# MCU.net
KiCad netlist of a schematic drawn in Altium Designer
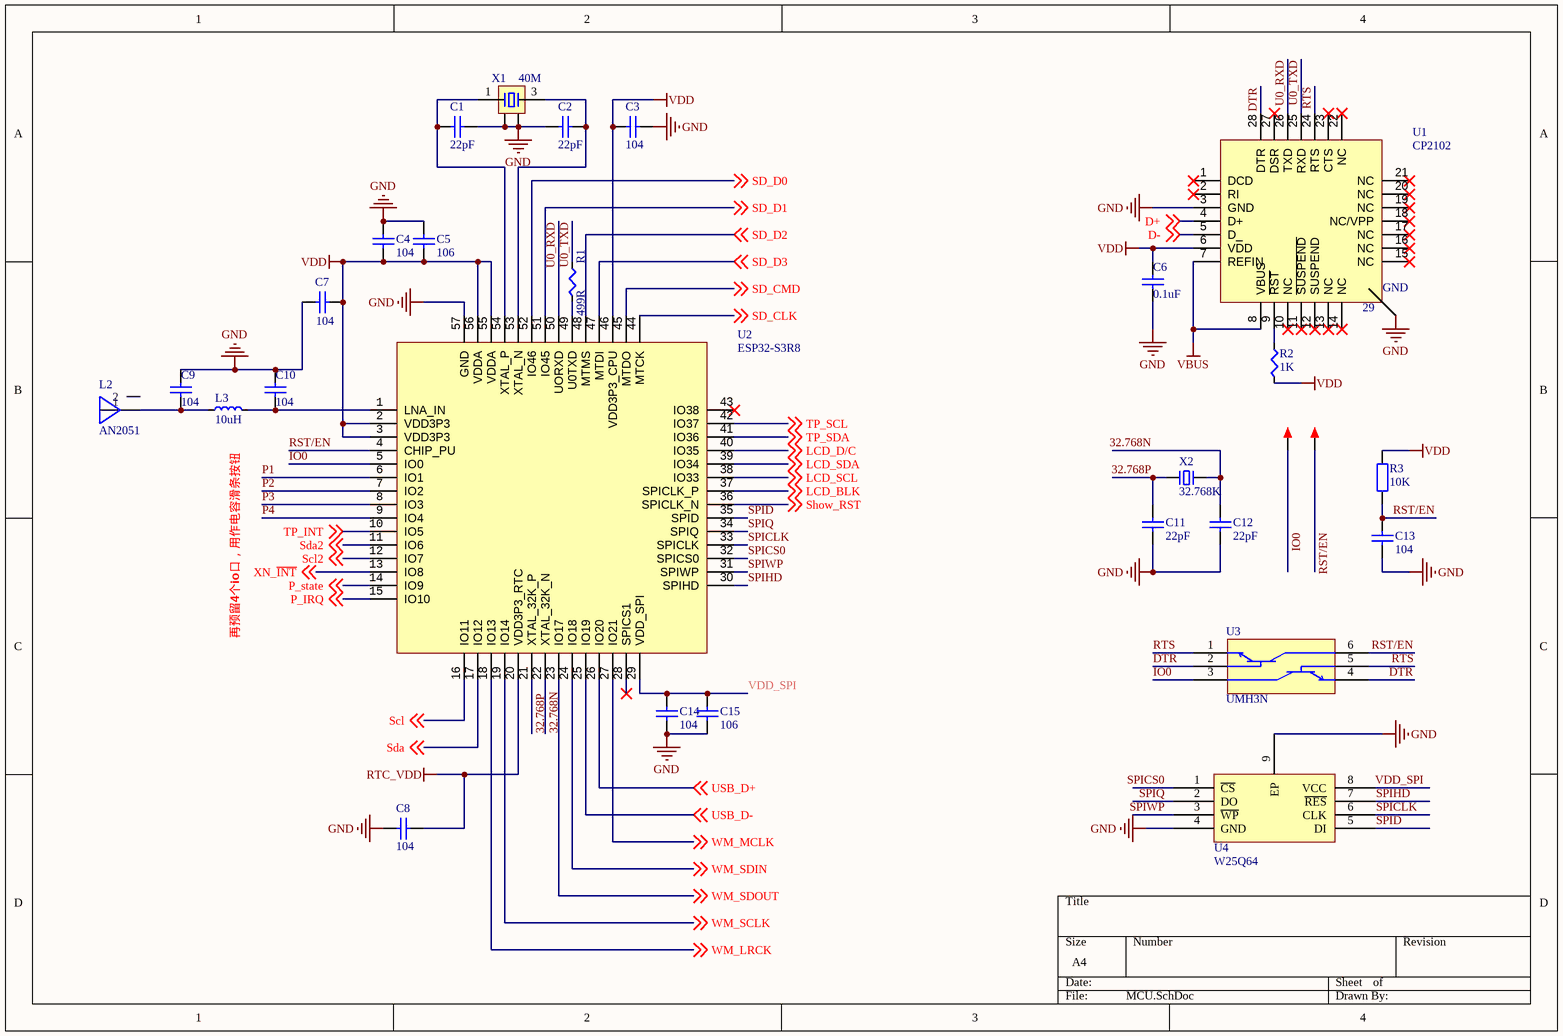
[diagram p0: MCU.SchDoc]

(export (version "E")
  (design (tool "Eeschema 10.0.6"))
  (components
    (comp (ref "C1")
      (value "22pF")
      (footprint "C 0603_L")
      (description "贴片电容")
      (libsource (lib "0.1 - 电阻-电容-电感") (part "C"))
    )
    (comp (ref "C2")
      (value "22pF")
      (footprint "C 0603_L")
      (description "贴片电容")
      (libsource (lib "0.1 - 电阻-电容-电感") (part "C"))
    )
    (comp (ref "C3")
      (value "104")
      (footprint "C 0603_L")
      (description "贴片电容")
      (libsource (lib "0.1 - 电阻-电容-电感") (part "C"))
    )
    (comp (ref "C4")
      (value "104")
      (footprint "C 0603_L")
      (description "贴片电容")
      (libsource (lib "0.1 - 电阻-电容-电感") (part "C"))
    )
    (comp (ref "C5")
      (value "106")
      (footprint "C 0603_L")
      (description "贴片电容")
      (libsource (lib "0.1 - 电阻-电容-电感") (part "C"))
    )
    (comp (ref "C6")
      (value "0.1uF")
      (footprint "C 0603_L")
      (description "贴片电容")
      (libsource (lib "0.1 - 电阻-电容-电感") (part "C"))
    )
    (comp (ref "C7")
      (value "104")
      (footprint "C 0603_L")
      (description "贴片电容")
      (libsource (lib "0.1 - 电阻-电容-电感") (part "C"))
    )
    (comp (ref "C8")
      (value "104")
      (footprint "C 0603_L")
      (description "贴片电容")
      (libsource (lib "0.1 - 电阻-电容-电感") (part "C"))
    )
    (comp (ref "C9")
      (value "104")
      (footprint "C 0603_L")
      (description "贴片电容")
      (libsource (lib "0.1 - 电阻-电容-电感") (part "C"))
    )
    (comp (ref "C10")
      (value "104")
      (footprint "C 0603_L")
      (description "贴片电容")
      (libsource (lib "0.1 - 电阻-电容-电感") (part "C"))
    )
    (comp (ref "C11")
      (value "22pF")
      (footprint "C 0603_L")
      (description "贴片电容")
      (libsource (lib "0.1 - 电阻-电容-电感") (part "C"))
    )
    (comp (ref "C12")
      (value "22pF")
      (footprint "C 0603_L")
      (description "贴片电容")
      (libsource (lib "0.1 - 电阻-电容-电感") (part "C"))
    )
    (comp (ref "C13")
      (value "104")
      (footprint "C 0603_L")
      (description "贴片电容")
      (libsource (lib "0.1 - 电阻-电容-电感") (part "C"))
    )
    (comp (ref "C14")
      (value "104")
      (footprint "C 0603_L")
      (description "贴片电容")
      (libsource (lib "0.1 - 电阻-电容-电感") (part "C"))
    )
    (comp (ref "C15")
      (value "106")
      (footprint "C 0603_L")
      (description "贴片电容")
      (libsource (lib "0.1 - 电阻-电容-电感") (part "C"))
    )
    (comp (ref "L2")
      (value "AN2051")
      (footprint "AN9520")
      (description "AN2051-245 2.4G蓝牙wifi 贴片 2051")
      (libsource (lib "1.8 - WiFi天线-SMA射频座") (part "AN2051"))
    )
    (comp (ref "L3")
      (value "10uH")
      (footprint "L 0603")
      (description "小功率贴片电感")
      (libsource (lib "0.1 - 电阻-电容-电感") (part "L"))
    )
    (comp (ref "R1")
      (value "499R")
      (footprint "R 0603_L")
      (description "贴片电阻")
      (libsource (lib "0.1 - 电阻-电容-电感") (part "R"))
    )
    (comp (ref "R2")
      (value "1K")
      (footprint "R 0603_L")
      (description "贴片电阻")
      (libsource (lib "0.1 - 电阻-电容-电感") (part "R"))
    )
    (comp (ref "R3")
      (value "10K")
      (footprint "R 0603_L")
      (description "贴片电阻")
      (libsource (lib "") (part "R_1"))
    )
    (comp (ref "TP1")
      (value "TEST")
      (footprint "TEST 1")
      (description "测试点")
      (libsource (lib "0.7 - 常用按键-开关-蜂鸣器-电池") (part "TEST"))
    )
    (comp (ref "TP2")
      (value "TEST")
      (footprint "TEST 1")
      (description "测试点")
      (libsource (lib "0.7 - 常用按键-开关-蜂鸣器-电池") (part "TEST"))
    )
    (comp (ref "U1")
      (value "CP2102")
      (footprint "QFN28 5x5_M")
      (description "USB转TTL")
      (libsource (lib "1.0 - 常见芯片") (part "CP2102"))
    )
    (comp (ref "U2")
      (value "ESP32-S3R8")
      (footprint "QFN56  7x7")
      (description "ESP32S3  7x7")
      (libsource (lib "1.0 - 常见芯片") (part "ESP32S3"))
    )
    (comp (ref "U3")
      (value "UMH3N")
      (footprint "SOT-363")
      (description "2NPN预偏式(双)")
      (libsource (lib "0.4 - 三极管-场效应管-可控硅") (part "UMH3N"))
    )
    (comp (ref "U4")
      (value "W25Q64")
      (footprint "WSON-8_L8.0-W6.0-P1.27-TL-EP")
      (description "C77819")
      (libsource (lib "1.0 - 常见芯片") (part "W25Q64——wson"))
    )
    (comp (ref "X1")
      (value "40M")
      (footprint "OSC 3225-4P")
      (description "4脚无源晶振")
      (libsource (lib "0.5 - 保险丝-晶振-光耦") (part "XTAL-4P"))
    )
    (comp (ref "X2")
      (value "32.768K")
      (footprint "OSC 3215-2P")
      (description "2脚无源脚晶振")
      (libsource (lib "0.5 - 保险丝-晶振-光耦") (part "XTAL-2P"))
    )
  )
  (nets
    (net (code "1") (name "/32.768N") (class "Default")
      (node (ref "C12") (pin "2") (pinfunction "2_2") (pintype "passive"))
      (node (ref "U2") (pin "22") (pinfunction "XTAL_32K_N_22") (pintype "passive"))
      (node (ref "X2") (pin "1") (pinfunction "1_1") (pintype "passive"))
    )
    (net (code "2") (name "/32.768P") (class "Default")
      (node (ref "C11") (pin "2") (pinfunction "2_2") (pintype "passive"))
      (node (ref "U2") (pin "21") (pinfunction "XTAL_32K_P_21") (pintype "passive"))
      (node (ref "X2") (pin "2") (pinfunction "2_2") (pintype "passive"))
    )
    (net (code "3") (name "/DTR") (class "Default")
      (node (ref "U1") (pin "28") (pinfunction "DTR_28") (pintype "passive"))
      (node (ref "U3") (pin "2") (pinfunction "B2_2") (pintype "passive"))
      (node (ref "U3") (pin "4") (pinfunction "E2_4") (pintype "passive"))
    )
    (net (code "4") (name "/IO0") (class "Default")
      (node (ref "TP1") (pin "1") (pinfunction "1_1") (pintype "passive"))
      (node (ref "U2") (pin "5") (pinfunction "IO0_5") (pintype "passive"))
      (node (ref "U3") (pin "3") (pinfunction "C2_3") (pintype "passive"))
    )
    (net (code "5") (name "/P1") (class "Default")
      (node (ref "U2") (pin "6") (pinfunction "IO1_6") (pintype "passive"))
    )
    (net (code "6") (name "/P2") (class "Default")
      (node (ref "U2") (pin "7") (pinfunction "IO2_7") (pintype "passive"))
    )
    (net (code "7") (name "/P3") (class "Default")
      (node (ref "U2") (pin "8") (pinfunction "IO3_8") (pintype "passive"))
    )
    (net (code "8") (name "/P4") (class "Default")
      (node (ref "U2") (pin "9") (pinfunction "IO4_9") (pintype "passive"))
    )
    (net (code "9") (name "/RST{slash}EN") (class "Default")
      (node (ref "C13") (pin "2") (pinfunction "2_2") (pintype "passive"))
      (node (ref "R3") (pin "1") (pinfunction "1_1") (pintype "passive"))
      (node (ref "TP2") (pin "1") (pinfunction "1_1") (pintype "passive"))
      (node (ref "U2") (pin "4") (pinfunction "CHIP_PU_4") (pintype "passive"))
      (node (ref "U3") (pin "6") (pinfunction "C1_6") (pintype "passive"))
    )
    (net (code "10") (name "/RTS") (class "Default")
      (node (ref "U1") (pin "24") (pinfunction "RTS_24") (pintype "passive"))
      (node (ref "U3") (pin "1") (pinfunction "E1_1") (pintype "passive"))
      (node (ref "U3") (pin "5") (pinfunction "B2_5") (pintype "passive"))
    )
    (net (code "11") (name "/SPICLK") (class "Default")
      (node (ref "U2") (pin "33") (pinfunction "SPICLK_33") (pintype "passive"))
      (node (ref "U4") (pin "6") (pinfunction "CLK_6") (pintype "passive"))
    )
    (net (code "12") (name "/SPICS0") (class "Default")
      (node (ref "U2") (pin "32") (pinfunction "SPICS0_32") (pintype "passive"))
      (node (ref "U4") (pin "1") (pinfunction "~{CS}_1") (pintype "passive"))
    )
    (net (code "13") (name "/SPID") (class "Default")
      (node (ref "U2") (pin "35") (pinfunction "SPID_35") (pintype "passive"))
      (node (ref "U4") (pin "5") (pinfunction "DI_5") (pintype "passive"))
    )
    (net (code "14") (name "/SPIHD") (class "Default")
      (node (ref "U2") (pin "30") (pinfunction "SPIHD_30") (pintype "passive"))
      (node (ref "U4") (pin "7") (pinfunction "~{RES}_7") (pintype "passive"))
    )
    (net (code "15") (name "/SPIQ") (class "Default")
      (node (ref "U2") (pin "34") (pinfunction "SPIQ_34") (pintype "passive"))
      (node (ref "U4") (pin "2") (pinfunction "DO_2") (pintype "passive"))
    )
    (net (code "16") (name "/SPIWP") (class "Default")
      (node (ref "U2") (pin "31") (pinfunction "SPIWP_31") (pintype "passive"))
      (node (ref "U4") (pin "3") (pinfunction "~{WP}_3") (pintype "passive"))
    )
    (net (code "17") (name "/U0_RXD") (class "Default")
      (node (ref "U1") (pin "26") (pinfunction "TXD_26") (pintype "passive"))
      (node (ref "U2") (pin "50") (pinfunction "UORXD_50") (pintype "passive"))
    )
    (net (code "18") (name "/U0_TXD") (class "Default")
      (node (ref "R1") (pin "2") (pinfunction "2_2") (pintype "passive"))
      (node (ref "U1") (pin "25") (pinfunction "RXD_25") (pintype "passive"))
    )
    (net (code "19") (name "/VDD_SPI") (class "Default")
      (node (ref "C14") (pin "2") (pinfunction "2_2") (pintype "passive"))
      (node (ref "C15") (pin "2") (pinfunction "2_2") (pintype "passive"))
      (node (ref "U2") (pin "29") (pinfunction "VDD_SPI_29") (pintype "passive"))
      (node (ref "U4") (pin "8") (pinfunction "VCC_8") (pintype "power_in"))
    )
    (net (code "20") (name "D+") (class "Default")
      (node (ref "U1") (pin "4") (pinfunction "D+_4") (pintype "passive"))
    )
    (net (code "21") (name "D-") (class "Default")
      (node (ref "U1") (pin "5") (pinfunction "D__5") (pintype "passive"))
    )
    (net (code "22") (name "GND") (class "Default")
      (node (ref "C1") (pin "2") (pinfunction "2_2") (pintype "passive"))
      (node (ref "C10") (pin "2") (pinfunction "2_2") (pintype "passive"))
      (node (ref "C11") (pin "1") (pinfunction "1_1") (pintype "passive"))
      (node (ref "C12") (pin "1") (pinfunction "1_1") (pintype "passive"))
      (node (ref "C13") (pin "1") (pinfunction "1_1") (pintype "passive"))
      (node (ref "C14") (pin "1") (pinfunction "1_1") (pintype "passive"))
      (node (ref "C15") (pin "1") (pinfunction "1_1") (pintype "passive"))
      (node (ref "C2") (pin "1") (pinfunction "1_1") (pintype "passive"))
      (node (ref "C3") (pin "2") (pinfunction "2_2") (pintype "passive"))
      (node (ref "C4") (pin "2") (pinfunction "2_2") (pintype "passive"))
      (node (ref "C5") (pin "2") (pinfunction "2_2") (pintype "passive"))
      (node (ref "C6") (pin "1") (pinfunction "1_1") (pintype "passive"))
      (node (ref "C7") (pin "1") (pinfunction "1_1") (pintype "passive"))
      (node (ref "C8") (pin "2") (pinfunction "2_2") (pintype "passive"))
      (node (ref "C9") (pin "2") (pinfunction "2_2") (pintype "passive"))
      (node (ref "U1") (pin "29") (pinfunction "GND_29") (pintype "passive"))
      (node (ref "U1") (pin "3") (pinfunction "GND_3") (pintype "passive"))
      (node (ref "U2") (pin "57") (pinfunction "GND_57") (pintype "passive"))
      (node (ref "U4") (pin "4") (pinfunction "GND_4") (pintype "power_in"))
      (node (ref "U4") (pin "9") (pinfunction "EP_9") (pintype "passive"))
      (node (ref "X1") (pin "2") (pinfunction "2_2") (pintype "passive"))
      (node (ref "X1") (pin "4") (pinfunction "4_4") (pintype "passive"))
    )
    (net (code "23") (name "LCD_BLK") (class "Default")
      (node (ref "U2") (pin "37") (pinfunction "SPICLK_P_37") (pintype "passive"))
    )
    (net (code "24") (name "LCD_D{slash}C") (class "Default")
      (node (ref "U2") (pin "40") (pinfunction "IO35_40") (pintype "passive"))
    )
    (net (code "25") (name "LCD_SCL") (class "Default")
      (node (ref "U2") (pin "38") (pinfunction "IO33_38") (pintype "passive"))
    )
    (net (code "26") (name "LCD_SDA") (class "Default")
      (node (ref "U2") (pin "39") (pinfunction "IO34_39") (pintype "passive"))
    )
    (net (code "27") (name "Net-(C9-Pad1)") (class "Default")
      (node (ref "C9") (pin "1") (pinfunction "1_1") (pintype "passive"))
      (node (ref "L2") (pin "1") (pinfunction "1_1") (pintype "passive"))
      (node (ref "L3") (pin "1") (pinfunction "1_1") (pintype "passive"))
    )
    (net (code "28") (name "Net-(U1-~{RST})") (class "Default")
      (node (ref "R2") (pin "2") (pinfunction "2_2") (pintype "passive"))
      (node (ref "U1") (pin "9") (pinfunction "~{RST}_9") (pintype "passive"))
    )
    (net (code "29") (name "Net-(U2-LNA_IN)") (class "Default")
      (node (ref "C10") (pin "1") (pinfunction "1_1") (pintype "passive"))
      (node (ref "L3") (pin "2") (pinfunction "2_2") (pintype "passive"))
      (node (ref "U2") (pin "1") (pinfunction "LNA_IN_1") (pintype "passive"))
    )
    (net (code "30") (name "Net-(U2-U0TXD)") (class "Default")
      (node (ref "R1") (pin "1") (pinfunction "1_1") (pintype "passive"))
      (node (ref "U2") (pin "49") (pinfunction "U0TXD_49") (pintype "passive"))
    )
    (net (code "31") (name "Net-(U2-XTAL_N)") (class "Default")
      (node (ref "C2") (pin "2") (pinfunction "2_2") (pintype "passive"))
      (node (ref "U2") (pin "53") (pinfunction "XTAL_N_53") (pintype "passive"))
      (node (ref "X1") (pin "3") (pinfunction "3_3") (pintype "passive"))
    )
    (net (code "32") (name "Net-(U2-XTAL_P)") (class "Default")
      (node (ref "C1") (pin "1") (pinfunction "1_1") (pintype "passive"))
      (node (ref "U2") (pin "54") (pinfunction "XTAL_P_54") (pintype "passive"))
      (node (ref "X1") (pin "1") (pinfunction "1_1") (pintype "passive"))
    )
    (net (code "33") (name "P_IRQ") (class "Default")
      (node (ref "U2") (pin "15") (pinfunction "IO10_15") (pintype "passive"))
    )
    (net (code "34") (name "P_state") (class "Default")
      (node (ref "U2") (pin "14") (pinfunction "IO9_14") (pintype "passive"))
    )
    (net (code "35") (name "RTC_VDD") (class "Default")
      (node (ref "C8") (pin "1") (pinfunction "1_1") (pintype "passive"))
      (node (ref "U2") (pin "20") (pinfunction "VDD3P3_RTC_20") (pintype "passive"))
    )
    (net (code "36") (name "SD_CLK") (class "Default")
      (node (ref "U2") (pin "44") (pinfunction "MTCK_44") (pintype "passive"))
    )
    (net (code "37") (name "SD_CMD") (class "Default")
      (node (ref "U2") (pin "45") (pinfunction "MTDO_45") (pintype "passive"))
    )
    (net (code "38") (name "SD_D0") (class "Default")
      (node (ref "U2") (pin "52") (pinfunction "IO46_52") (pintype "passive"))
    )
    (net (code "39") (name "SD_D1") (class "Default")
      (node (ref "U2") (pin "51") (pinfunction "IO45_51") (pintype "passive"))
    )
    (net (code "40") (name "SD_D2") (class "Default")
      (node (ref "U2") (pin "48") (pinfunction "MTMS_48") (pintype "passive"))
    )
    (net (code "41") (name "SD_D3") (class "Default")
      (node (ref "U2") (pin "47") (pinfunction "MTDI_47") (pintype "passive"))
    )
    (net (code "42") (name "Scl") (class "Default")
      (node (ref "U2") (pin "16") (pinfunction "IO11_16") (pintype "passive"))
    )
    (net (code "43") (name "Scl2") (class "Default")
      (node (ref "U2") (pin "12") (pinfunction "IO7_12") (pintype "passive"))
    )
    (net (code "44") (name "Sda") (class "Default")
      (node (ref "U2") (pin "17") (pinfunction "IO12_17") (pintype "passive"))
    )
    (net (code "45") (name "Sda2") (class "Default")
      (node (ref "U2") (pin "11") (pinfunction "IO6_11") (pintype "passive"))
    )
    (net (code "46") (name "Show_RST") (class "Default")
      (node (ref "U2") (pin "36") (pinfunction "SPICLK_N_36") (pintype "passive"))
    )
    (net (code "47") (name "TP_INT") (class "Default")
      (node (ref "U2") (pin "10") (pinfunction "IO5_10") (pintype "passive"))
    )
    (net (code "48") (name "TP_SCL") (class "Default")
      (node (ref "U2") (pin "42") (pinfunction "IO37_42") (pintype "passive"))
    )
    (net (code "49") (name "TP_SDA") (class "Default")
      (node (ref "U2") (pin "41") (pinfunction "IO36_41") (pintype "passive"))
    )
    (net (code "50") (name "USB_D+") (class "Default")
      (node (ref "U2") (pin "26") (pinfunction "IO20_26") (pintype "passive"))
    )
    (net (code "51") (name "USB_D-") (class "Default")
      (node (ref "U2") (pin "25") (pinfunction "IO19_25") (pintype "passive"))
    )
    (net (code "52") (name "VBUS") (class "Default")
      (node (ref "U1") (pin "7") (pinfunction "REFIN_7") (pintype "passive"))
      (node (ref "U1") (pin "8") (pinfunction "VBUS_8") (pintype "passive"))
    )
    (net (code "53") (name "VDD") (class "Default")
      (node (ref "C3") (pin "1") (pinfunction "1_1") (pintype "passive"))
      (node (ref "C4") (pin "1") (pinfunction "1_1") (pintype "passive"))
      (node (ref "C5") (pin "1") (pinfunction "1_1") (pintype "passive"))
      (node (ref "C6") (pin "2") (pinfunction "2_2") (pintype "passive"))
      (node (ref "C7") (pin "2") (pinfunction "2_2") (pintype "passive"))
      (node (ref "R2") (pin "1") (pinfunction "1_1") (pintype "passive"))
      (node (ref "R3") (pin "2") (pinfunction "2_2") (pintype "passive"))
      (node (ref "U1") (pin "6") (pinfunction "VDD_6") (pintype "passive"))
      (node (ref "U2") (pin "2") (pinfunction "VDD3P3_2") (pintype "passive"))
      (node (ref "U2") (pin "3") (pinfunction "VDD3P3_3") (pintype "passive"))
      (node (ref "U2") (pin "46") (pinfunction "VDD3P3_CPU_46") (pintype "passive"))
      (node (ref "U2") (pin "55") (pinfunction "VDDA_55") (pintype "passive"))
      (node (ref "U2") (pin "56") (pinfunction "VDDA_56") (pintype "passive"))
    )
    (net (code "54") (name "WM_LRCK") (class "Default")
      (node (ref "U2") (pin "18") (pinfunction "IO13_18") (pintype "passive"))
    )
    (net (code "55") (name "WM_MCLK") (class "Default")
      (node (ref "U2") (pin "27") (pinfunction "IO21_27") (pintype "passive"))
    )
    (net (code "56") (name "WM_SCLK") (class "Default")
      (node (ref "U2") (pin "19") (pinfunction "IO14_19") (pintype "passive"))
    )
    (net (code "57") (name "WM_SDIN") (class "Default")
      (node (ref "U2") (pin "24") (pinfunction "IO18_24") (pintype "passive"))
    )
    (net (code "58") (name "WM_SDOUT") (class "Default")
      (node (ref "U2") (pin "23") (pinfunction "IO17_23") (pintype "passive"))
    )
    (net (code "59") (name "XN_~{INT}") (class "Default")
      (node (ref "U2") (pin "13") (pinfunction "IO8_13") (pintype "passive"))
    )
    (net (code "60") (name "unconnected-(L2-Pad2)") (class "Default")
      (node (ref "L2") (pin "2") (pinfunction "2_2") (pintype "passive"))
    )
    (net (code "61") (name "unconnected-(U1-CTS-Pad23)") (class "Default")
      (node (ref "U1") (pin "23") (pinfunction "CTS_23") (pintype "passive+no_connect"))
    )
    (net (code "62") (name "unconnected-(U1-DCD-Pad1)") (class "Default")
      (node (ref "U1") (pin "1") (pinfunction "DCD_1") (pintype "passive+no_connect"))
    )
    (net (code "63") (name "unconnected-(U1-DSR-Pad27)") (class "Default")
      (node (ref "U1") (pin "27") (pinfunction "DSR_27") (pintype "passive+no_connect"))
    )
    (net (code "64") (name "unconnected-(U1-NC-Pad10)") (class "Default")
      (node (ref "U1") (pin "10") (pinfunction "NC_10") (pintype "passive+no_connect"))
    )
    (net (code "65") (name "unconnected-(U1-NC-Pad13)") (class "Default")
      (node (ref "U1") (pin "13") (pinfunction "NC_13") (pintype "passive+no_connect"))
    )
    (net (code "66") (name "unconnected-(U1-NC-Pad14)") (class "Default")
      (node (ref "U1") (pin "14") (pinfunction "NC_14") (pintype "passive+no_connect"))
    )
    (net (code "67") (name "unconnected-(U1-NC-Pad15)") (class "Default")
      (node (ref "U1") (pin "15") (pinfunction "NC_15") (pintype "passive+no_connect"))
    )
    (net (code "68") (name "unconnected-(U1-NC-Pad16)") (class "Default")
      (node (ref "U1") (pin "16") (pinfunction "NC_16") (pintype "passive+no_connect"))
    )
    (net (code "69") (name "unconnected-(U1-NC-Pad17)") (class "Default")
      (node (ref "U1") (pin "17") (pinfunction "NC_17") (pintype "passive+no_connect"))
    )
    (net (code "70") (name "unconnected-(U1-NC-Pad19)") (class "Default")
      (node (ref "U1") (pin "19") (pinfunction "NC_19") (pintype "passive+no_connect"))
    )
    (net (code "71") (name "unconnected-(U1-NC-Pad20)") (class "Default")
      (node (ref "U1") (pin "20") (pinfunction "NC_20") (pintype "passive+no_connect"))
    )
    (net (code "72") (name "unconnected-(U1-NC-Pad21)") (class "Default")
      (node (ref "U1") (pin "21") (pinfunction "NC_21") (pintype "passive+no_connect"))
    )
    (net (code "73") (name "unconnected-(U1-NC-Pad22)") (class "Default")
      (node (ref "U1") (pin "22") (pinfunction "NC_22") (pintype "passive+no_connect"))
    )
    (net (code "74") (name "unconnected-(U1-NC{slash}VPP-Pad18)") (class "Default")
      (node (ref "U1") (pin "18") (pinfunction "NC/VPP_18") (pintype "passive+no_connect"))
    )
    (net (code "75") (name "unconnected-(U1-RI-Pad2)") (class "Default")
      (node (ref "U1") (pin "2") (pinfunction "RI_2") (pintype "passive+no_connect"))
    )
    (net (code "76") (name "unconnected-(U1-SUSPEND-Pad12)") (class "Default")
      (node (ref "U1") (pin "12") (pinfunction "SUSPEND_12") (pintype "passive+no_connect"))
    )
    (net (code "77") (name "unconnected-(U1-~{SUSPEND}-Pad11)") (class "Default")
      (node (ref "U1") (pin "11") (pinfunction "~{SUSPEND}_11") (pintype "passive+no_connect"))
    )
    (net (code "78") (name "unconnected-(U2-IO38-Pad43)") (class "Default")
      (node (ref "U2") (pin "43") (pinfunction "IO38_43") (pintype "passive+no_connect"))
    )
    (net (code "79") (name "unconnected-(U2-SPICS1-Pad28)") (class "Default")
      (node (ref "U2") (pin "28") (pinfunction "SPICS1_28") (pintype "passive+no_connect"))
    )
  )
)
